# RF_Frontend_2.net
KiCad netlist of a schematic drawn in Altium Designer
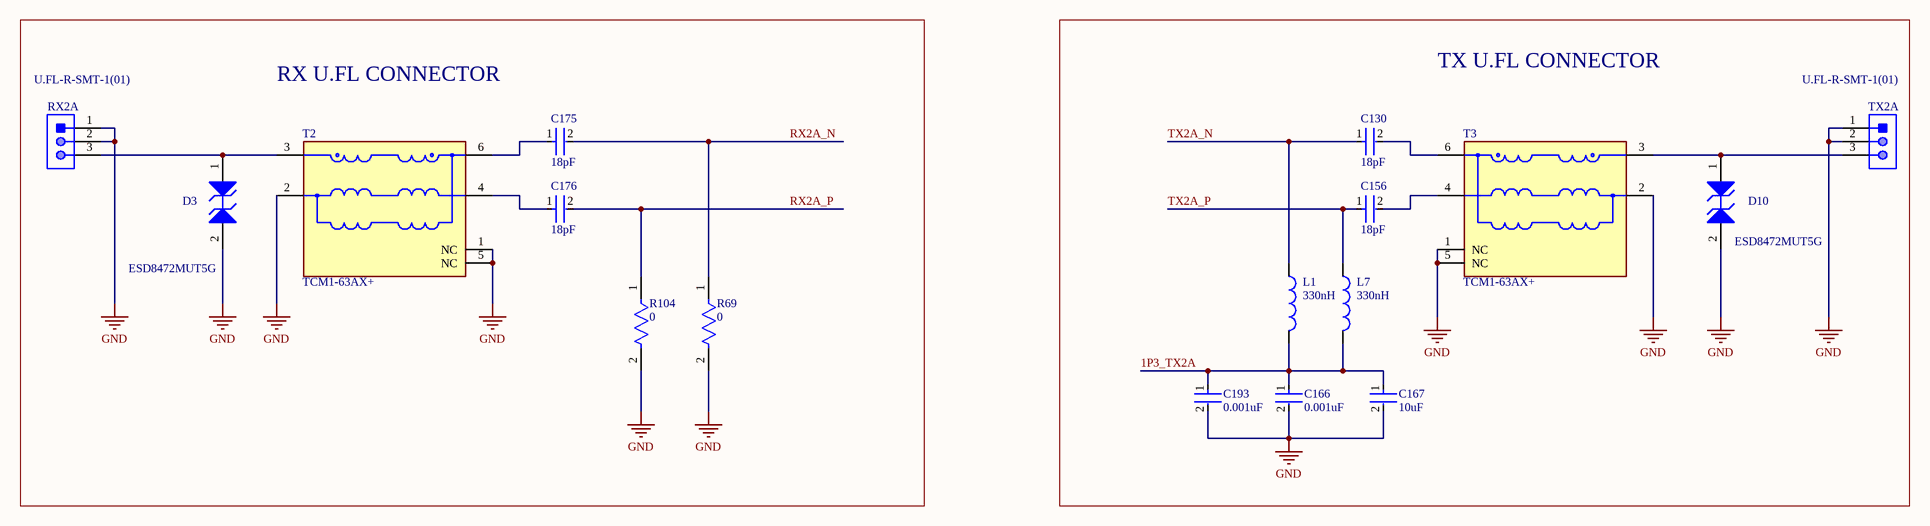
[diagram p0: RF Frontend 2.SchDoc]

(export (version "E")
  (design (tool "Eeschema 10.0.6"))
  (components
    (comp (ref "C130")
      (value "18pF")
      (footprint "FP-GRM033-0_03-IPC_A")
      (description "Chip Multilayer Ceramic Capacitors for General Purpose, 0201, 18pF, C0G, 30ppm/°C, 5%, 50V")
      (fields (field (name "TOLERANCE") "5%") (field (name "VOLTAGE") "50V"))
      (libsource (lib "Altium Content Vault") (part "b4654b650e69147ec39a6b967a45e02"))
    )
    (comp (ref "C156")
      (value "18pF")
      (footprint "FP-GRM033-0_03-IPC_A")
      (description "Chip Multilayer Ceramic Capacitors for General Purpose, 0201, 18pF, C0G, 30ppm/°C, 5%, 50V")
      (fields (field (name "TOLERANCE") "5%") (field (name "VOLTAGE") "50V"))
      (libsource (lib "Altium Content Vault") (part "b4654b650e69147ec39a6b967a45e02"))
    )
    (comp (ref "C166")
      (value "0.001uF")
      (footprint "FP-GRM033-0_03-MFG")
      (description "Chip Multilayer Ceramic Capacitors for General Purpose, 0201, 1000pF, X7R, 15%, 10%, 25V")
      (fields (field (name "TOLERANCE") "10%") (field (name "VOLTAGE") "25V"))
      (libsource (lib "Altium Content Vault") (part "b4654b650e69147ec39a6b967a45e02"))
    )
    (comp (ref "C167")
      (value "10uF")
      (footprint "FP-GRM188-0_1-e0_2_0_55-IPC_C")
      (description "Chip Multilayer Ceramic Capacitors for General Purpose, 0603, 10uF, X5R, 15%, 20%, 6.3V")
      (fields (field (name "VOLTAGE") "6.3V") (field (name "TOLERANCE") "20%"))
      (libsource (lib "Altium Content Vault") (part "02cd4be3c70576c341d710602a673aa"))
    )
    (comp (ref "C175")
      (value "18pF")
      (footprint "FP-GRM033-0_03-IPC_A")
      (description "Chip Multilayer Ceramic Capacitors for General Purpose, 0201, 18pF, C0G, 30ppm/°C, 5%, 50V")
      (fields (field (name "TOLERANCE") "5%") (field (name "VOLTAGE") "50V"))
      (libsource (lib "Altium Content Vault") (part "b4654b650e69147ec39a6b967a45e02"))
    )
    (comp (ref "C176")
      (value "18pF")
      (footprint "FP-GRM033-0_03-IPC_A")
      (description "Chip Multilayer Ceramic Capacitors for General Purpose, 0201, 18pF, C0G, 30ppm/°C, 5%, 50V")
      (fields (field (name "TOLERANCE") "5%") (field (name "VOLTAGE") "50V"))
      (libsource (lib "Altium Content Vault") (part "b4654b650e69147ec39a6b967a45e02"))
    )
    (comp (ref "C193")
      (value "0.001uF")
      (footprint "FP-GRM033-0_03-MFG")
      (description "Chip Multilayer Ceramic Capacitors for General Purpose, 0201, 1000pF, X7R, 15%, 10%, 25V")
      (fields (field (name "TOLERANCE") "10%") (field (name "VOLTAGE") "25V"))
      (libsource (lib "Altium Content Vault") (part "b4654b650e69147ec39a6b967a45e02"))
    )
    (comp (ref "D3")
      (value "ESD8472MUT5G")
      (footprint "ONSC-X3DFN-2-152AF-01_V")
      (fields (field (name "MANUFACTURER") "On Semiconductor"))
      (libsource (lib "Altium Content Vault") (part "ONSC-A1A2-2"))
    )
    (comp (ref "D10")
      (value "ESD8472MUT5G")
      (footprint "ONSC-X3DFN-2-152AF-01_V")
      (fields (field (name "MANUFACTURER") "On Semiconductor"))
      (libsource (lib "Altium Content Vault") (part "ONSC-A1A2-2"))
    )
    (comp (ref "L1")
      (value "330nH")
      (footprint "INDC2317X140N")
      (description "Inductor")
      (fields (field (name "PUBLISHER") "Altium Limited"))
      (libsource (lib "Miscellaneous Devices") (part "Inductor"))
    )
    (comp (ref "L7")
      (value "330nH")
      (footprint "INDC2317X140N")
      (description "Inductor")
      (fields (field (name "PUBLISHER") "Altium Limited"))
      (libsource (lib "Miscellaneous Devices") (part "Inductor"))
    )
    (comp (ref "R69")
      (value "0")
      (footprint "FP-ERJ1GN-MFG")
      (description "RES SMD 0 OHM JUMPER 1/20W 0201")
      (fields (field (name "TOLERANCE") "1%"))
      (libsource (lib "Altium Content Vault") (part "1029c3af85768c4190bb7ad29bc67b5"))
    )
    (comp (ref "R104")
      (value "0")
      (footprint "FP-ERJ1GN-MFG")
      (description "RES SMD 0 OHM JUMPER 1/20W 0201")
      (fields (field (name "TOLERANCE") "1%"))
      (libsource (lib "Altium Content Vault") (part "1029c3af85768c4190bb7ad29bc67b5"))
    )
    (comp (ref "RX2A")
      (value "U.FL-R-SMT-1(01)")
      (footprint "HRS-U.FL-R-SMT-3_V")
      (description "Ultra Small Coaxial Connector, 6 GHz, -40 to 90 degC, 3-Pin SMD, RoHS, Bulk")
      (fields (field (name "MANUFACTURER") "Hirose Electric"))
      (libsource (lib "") (part "CN-1P-M-R3_1"))
    )
    (comp (ref "T2")
      (value "TCM1-63AX+")
      (footprint "FP-TCM1-63AX+-MFG")
      (description "1:1 CORE & WIRE Transformer, 10 - 6000 MHz, 50Ω")
      (fields
        (field (name "MANUFACTURER") "Mini-Circuits")
        (field (name "OCTOPART") "https://octopart.com/tcm1-63ax%2B-mini-circuits-107315723")
      )
      (libsource (lib "") (part "572340aedd709dbafee1a1d3331a406_1"))
    )
    (comp (ref "T3")
      (value "TCM1-63AX+")
      (footprint "FP-TCM1-63AX+-MFG")
      (description "1:1 CORE & WIRE Transformer, 10 - 6000 MHz, 50Ω")
      (fields
        (field (name "MANUFACTURER") "Mini-Circuits")
        (field (name "OCTOPART") "https://octopart.com/tcm1-63ax%2B-mini-circuits-107315723")
      )
      (libsource (lib "Altium Content Vault") (part "572340aedd709dbafee1a1d3331a406"))
    )
    (comp (ref "TX2A")
      (value "U.FL-R-SMT-1(01)")
      (footprint "HRS-U.FL-R-SMT-3_V")
      (description "Ultra Small Coaxial Connector, 6 GHz, -40 to 90 degC, 3-Pin SMD, RoHS, Bulk")
      (fields (field (name "MANUFACTURER") "Hirose Electric"))
      (libsource (lib "Altium Content Vault") (part "CN-1P-M-R3"))
    )
  )
  (nets
    (net (code "1") (name "/1P3_TX2A") (class "Default")
      (node (ref "C166") (pin "1") (pinfunction "1_1") (pintype "passive"))
      (node (ref "C167") (pin "1") (pinfunction "1_1") (pintype "passive"))
      (node (ref "C193") (pin "1") (pinfunction "1_1") (pintype "passive"))
      (node (ref "L1") (pin "2") (pinfunction "2_2") (pintype "passive"))
      (node (ref "L7") (pin "2") (pinfunction "2_2") (pintype "passive"))
    )
    (net (code "2") (name "/RX2A_N") (class "Default")
      (node (ref "C175") (pin "2") (pinfunction "2_2") (pintype "passive"))
      (node (ref "R69") (pin "1") (pinfunction "1_1") (pintype "passive"))
    )
    (net (code "3") (name "/RX2A_P") (class "Default")
      (node (ref "C176") (pin "2") (pinfunction "2_2") (pintype "passive"))
      (node (ref "R104") (pin "1") (pinfunction "1_1") (pintype "passive"))
    )
    (net (code "4") (name "/TX2A_N") (class "Default")
      (node (ref "C130") (pin "1") (pinfunction "1_1") (pintype "passive"))
      (node (ref "L1") (pin "1") (pinfunction "1_1") (pintype "passive"))
    )
    (net (code "5") (name "/TX2A_P") (class "Default")
      (node (ref "C156") (pin "1") (pinfunction "1_1") (pintype "passive"))
      (node (ref "L7") (pin "1") (pinfunction "1_1") (pintype "passive"))
    )
    (net (code "6") (name "GND") (class "Default")
      (node (ref "C166") (pin "2") (pinfunction "2_2") (pintype "passive"))
      (node (ref "C167") (pin "2") (pinfunction "2_2") (pintype "passive"))
      (node (ref "C193") (pin "2") (pinfunction "2_2") (pintype "passive"))
      (node (ref "D10") (pin "2") (pinfunction "A2_2") (pintype "passive"))
      (node (ref "D3") (pin "2") (pinfunction "A2_2") (pintype "passive"))
      (node (ref "R104") (pin "2") (pinfunction "2_2") (pintype "passive"))
      (node (ref "R69") (pin "2") (pinfunction "2_2") (pintype "passive"))
      (node (ref "RX2A") (pin "1") (pinfunction "1_1") (pintype "passive"))
      (node (ref "RX2A") (pin "2") (pinfunction "2_2") (pintype "passive"))
      (node (ref "T2") (pin "1") (pinfunction "NC_1") (pintype "passive"))
      (node (ref "T2") (pin "2") (pinfunction "GND_2") (pintype "passive"))
      (node (ref "T2") (pin "5") (pinfunction "NC_5") (pintype "passive"))
      (node (ref "T3") (pin "1") (pinfunction "NC_1") (pintype "passive"))
      (node (ref "T3") (pin "2") (pinfunction "GND_2") (pintype "passive"))
      (node (ref "T3") (pin "5") (pinfunction "NC_5") (pintype "passive"))
      (node (ref "TX2A") (pin "1") (pinfunction "1_1") (pintype "passive"))
      (node (ref "TX2A") (pin "2") (pinfunction "2_2") (pintype "passive"))
    )
    (net (code "7") (name "Net-(D3-A1)") (class "Default")
      (node (ref "D3") (pin "1") (pinfunction "A1_1") (pintype "passive"))
      (node (ref "RX2A") (pin "3") (pinfunction "3_3") (pintype "passive"))
      (node (ref "T2") (pin "3") (pinfunction "PRIMARY_DOT_3") (pintype "passive"))
    )
    (net (code "8") (name "Net-(D10-A1)") (class "Default")
      (node (ref "D10") (pin "1") (pinfunction "A1_1") (pintype "passive"))
      (node (ref "T3") (pin "3") (pinfunction "PRIMARY_DOT_3") (pintype "passive"))
      (node (ref "TX2A") (pin "3") (pinfunction "3_3") (pintype "passive"))
    )
    (net (code "9") (name "Net-(T2-SECONDARY)") (class "Default")
      (node (ref "C176") (pin "1") (pinfunction "1_1") (pintype "passive"))
      (node (ref "T2") (pin "4") (pinfunction "SECONDARY_4") (pintype "passive"))
    )
    (net (code "10") (name "Net-(T2-SECONDARY_DOT)") (class "Default")
      (node (ref "C175") (pin "1") (pinfunction "1_1") (pintype "passive"))
      (node (ref "T2") (pin "6") (pinfunction "SECONDARY_DOT_6") (pintype "passive"))
    )
    (net (code "11") (name "Net-(T3-SECONDARY)") (class "Default")
      (node (ref "C156") (pin "2") (pinfunction "2_2") (pintype "passive"))
      (node (ref "T3") (pin "4") (pinfunction "SECONDARY_4") (pintype "passive"))
    )
    (net (code "12") (name "Net-(T3-SECONDARY_DOT)") (class "Default")
      (node (ref "C130") (pin "2") (pinfunction "2_2") (pintype "passive"))
      (node (ref "T3") (pin "6") (pinfunction "SECONDARY_DOT_6") (pintype "passive"))
    )
  )
)
